# Satellite_Transceiver_Breakout__Swarm_M1.net
KiCad netlist of a schematic drawn in EAGLE
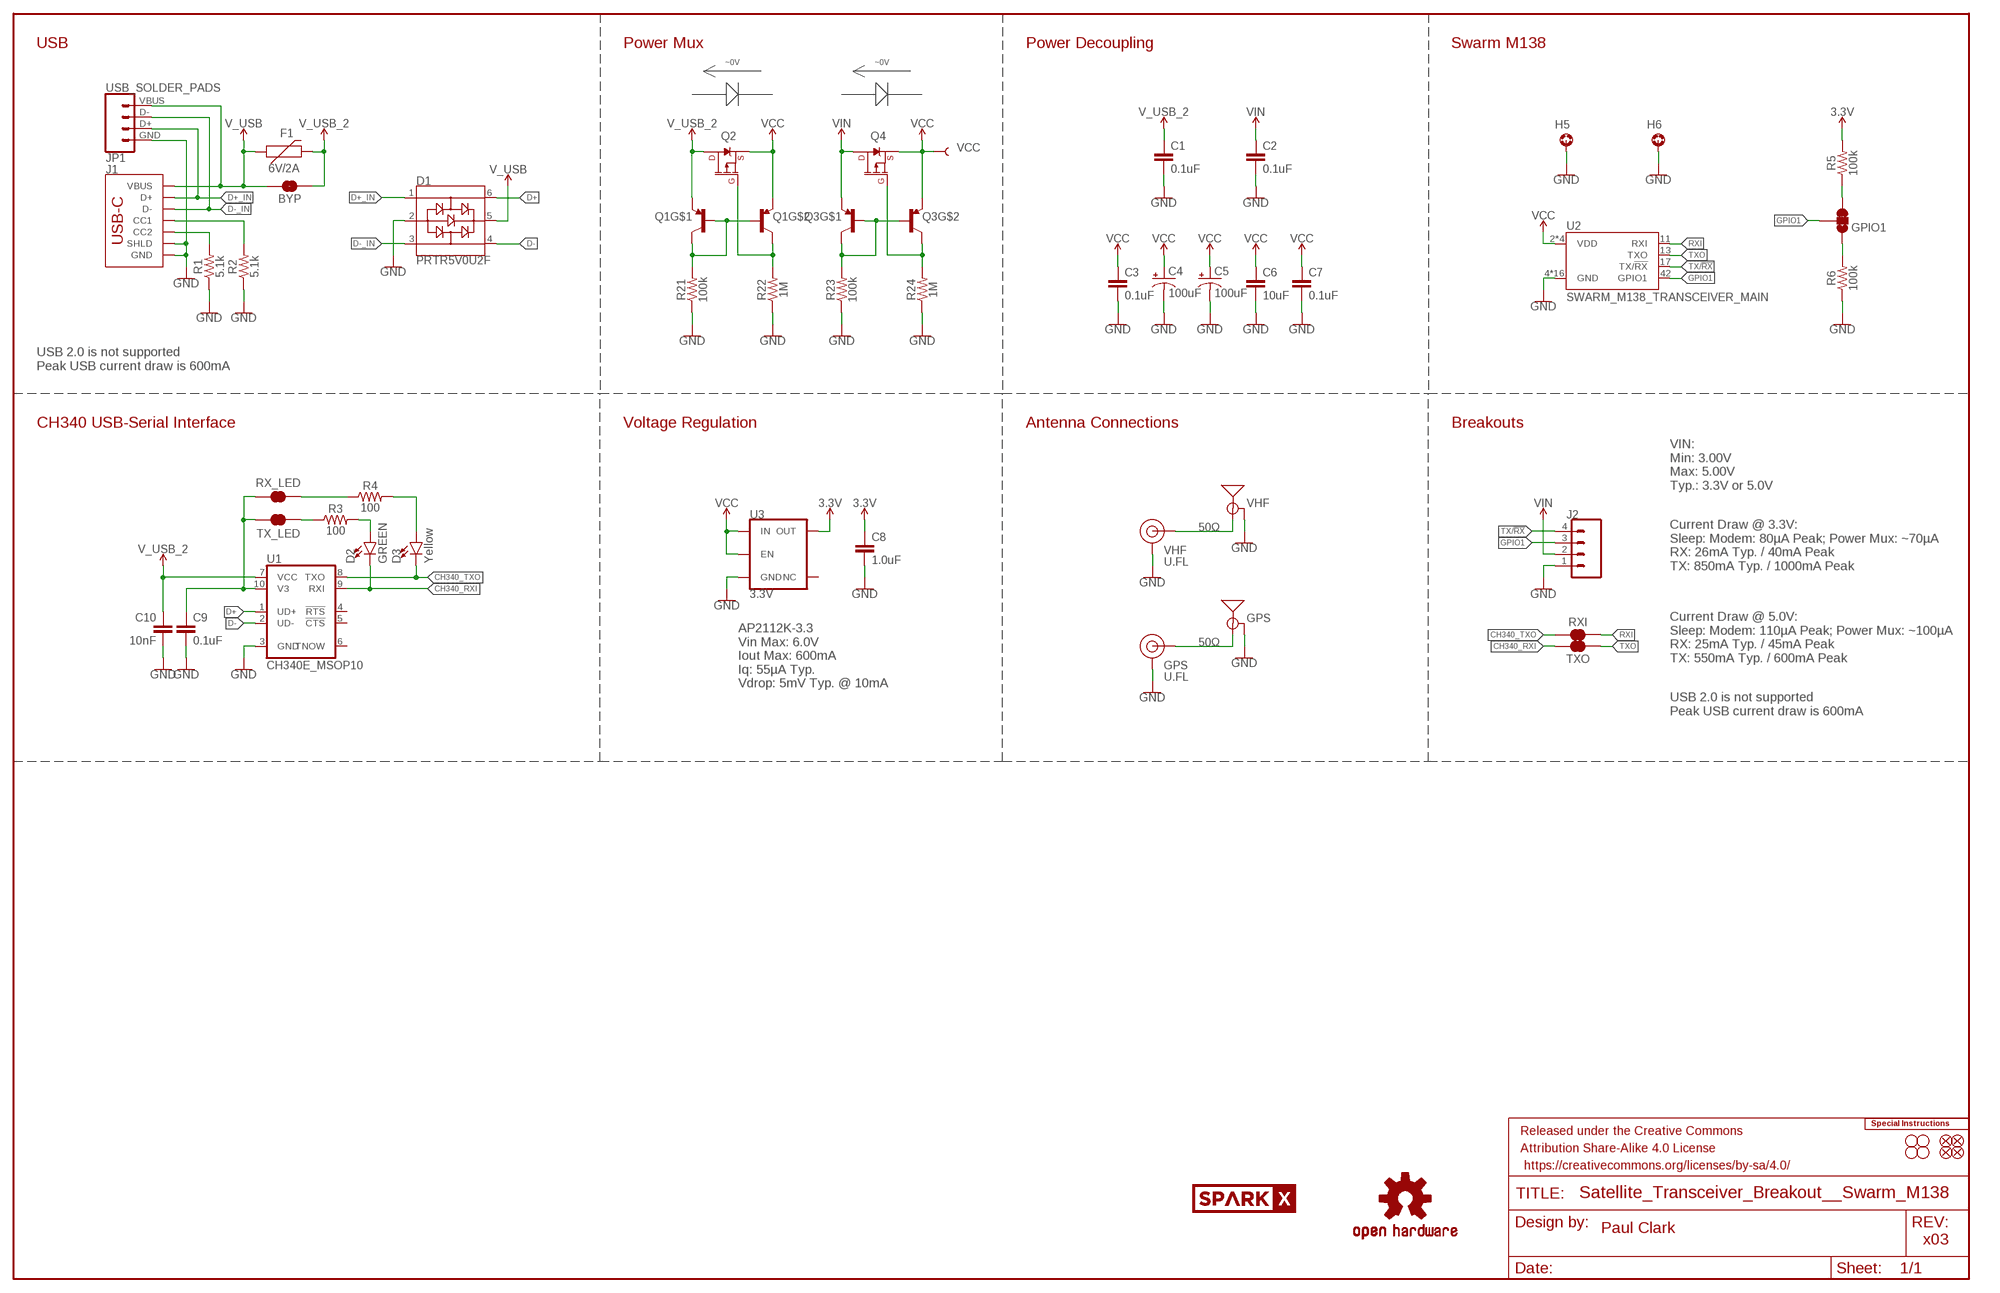
[diagram p0: schematic, sheet 1]

(export (version "E")
  (design (tool "Eeschema 10.0.6"))
  (components
    (comp (ref "BYP")
      (value "JUMPER-SMT_2_NO_SILK")
      (footprint "eagle-import:SMT-JUMPER_2_NO_SILK")
      (libsource (lib "eagle-import") (part "JUMPER-SMT_2_NO_SILK"))
    )
    (comp (ref "C1")
      (value "0.1uF")
      (footprint "eagle-import:0603")
      (libsource (lib "eagle-import") (part "0.1UF-0603-25V-5%"))
    )
    (comp (ref "C2")
      (value "0.1uF")
      (footprint "eagle-import:0603")
      (libsource (lib "eagle-import") (part "0.1UF-0603-25V-5%"))
    )
    (comp (ref "C3")
      (value "0.1uF")
      (footprint "eagle-import:0603")
      (libsource (lib "eagle-import") (part "0.1UF-0603-25V-5%"))
    )
    (comp (ref "C4")
      (value "100uF")
      (footprint "eagle-import:PANASONIC_D")
      (libsource (lib "eagle-import") (part "100UF-POLAR-25V-20%(ELEC)"))
    )
    (comp (ref "C5")
      (value "100uF")
      (footprint "eagle-import:PANASONIC_D")
      (libsource (lib "eagle-import") (part "100UF-POLAR-25V-20%(ELEC)"))
    )
    (comp (ref "C6")
      (value "10uF")
      (footprint "eagle-import:0603")
      (libsource (lib "eagle-import") (part "10UF-0603-6.3V-20%"))
    )
    (comp (ref "C7")
      (value "0.1uF")
      (footprint "eagle-import:0603")
      (libsource (lib "eagle-import") (part "0.1UF-0603-25V-5%"))
    )
    (comp (ref "C8")
      (value "1.0uF")
      (footprint "eagle-import:0603")
      (libsource (lib "eagle-import") (part "1.0UF-0603-16V-10%-X7R"))
    )
    (comp (ref "C9")
      (value "0.1uF")
      (footprint "eagle-import:0603")
      (libsource (lib "eagle-import") (part "0.1UF-0603-25V-5%"))
    )
    (comp (ref "C10")
      (value "10nF")
      (footprint "eagle-import:0603")
      (libsource (lib "eagle-import") (part "10NF-0603-50V-10%"))
    )
    (comp (ref "D1")
      (value "PRTR5V0U2F")
      (footprint "eagle-import:SOT886")
      (libsource (lib "eagle-import") (part "PRTR5V0U2F"))
    )
    (comp (ref "D2")
      (value "GREEN")
      (footprint "eagle-import:LED-0603")
      (libsource (lib "eagle-import") (part "LED-GREEN0603"))
    )
    (comp (ref "D3")
      (value "Yellow")
      (footprint "eagle-import:LED-0603")
      (libsource (lib "eagle-import") (part "LED-YELLOW0603"))
    )
    (comp (ref "E1")
      (value "VHF")
      (footprint "eagle-import:SMA-EDGE")
      (libsource (lib "eagle-import") (part "ANTENNA-SMA-GROUNDEDEDGE_SMA"))
    )
    (comp (ref "E2")
      (value "GPS")
      (footprint "eagle-import:SMA-EDGE")
      (libsource (lib "eagle-import") (part "ANTENNA-SMA-GROUNDEDEDGE_SMA"))
    )
    (comp (ref "F1")
      (value "6V/2A")
      (footprint "eagle-import:1210")
      (libsource (lib "eagle-import") (part "PPTC_6V2A"))
    )
    (comp (ref "FD1")
      (value "FIDUCIAL1X2")
      (footprint "eagle-import:FIDUCIAL-1X2")
      (libsource (lib "eagle-import") (part "FIDUCIAL1X2"))
    )
    (comp (ref "FD2")
      (value "FIDUCIAL1X2")
      (footprint "eagle-import:FIDUCIAL-1X2")
      (libsource (lib "eagle-import") (part "FIDUCIAL1X2"))
    )
    (comp (ref "FD3")
      (value "FIDUCIAL1X2")
      (footprint "eagle-import:FIDUCIAL-1X2")
      (libsource (lib "eagle-import") (part "FIDUCIAL1X2"))
    )
    (comp (ref "FD4")
      (value "FIDUCIAL1X2")
      (footprint "eagle-import:FIDUCIAL-1X2")
      (libsource (lib "eagle-import") (part "FIDUCIAL1X2"))
    )
    (comp (ref "FRAME1")
      (value "FRAME-LEDGER")
      (footprint "eagle-import:CREATIVE_COMMONS")
      (libsource (lib "eagle-import") (part "FRAME-LEDGER"))
    )
    (comp (ref "GPIO1")
      (value "JUMPER-SMT_3_1-NC_TRACE_SILK")
      (footprint "eagle-import:SMT-JUMPER_3_1-NC_TRACE_SILK")
      (libsource (lib "eagle-import") (part "JUMPER-SMT_3_1-NC_TRACE_SILK"))
    )
    (comp (ref "GPS")
      (value "U.FL")
      (footprint "eagle-import:U.FL")
      (libsource (lib "eagle-import") (part "U.FL2PIN"))
    )
    (comp (ref "H1")
      (value "STAND-OFF")
      (footprint "eagle-import:STAND-OFF")
      (libsource (lib "eagle-import") (part "STAND-OFF"))
    )
    (comp (ref "H2")
      (value "STAND-OFF")
      (footprint "eagle-import:STAND-OFF")
      (libsource (lib "eagle-import") (part "STAND-OFF"))
    )
    (comp (ref "H3")
      (value "STAND-OFF")
      (footprint "eagle-import:STAND-OFF")
      (libsource (lib "eagle-import") (part "STAND-OFF"))
    )
    (comp (ref "H4")
      (value "STAND-OFF")
      (footprint "eagle-import:STAND-OFF")
      (libsource (lib "eagle-import") (part "STAND-OFF"))
    )
    (comp (ref "H5")
      (value "STAND-OFF-REFLOW-M2.5_1.5MM_TALL")
      (footprint "eagle-import:STAND-OFF-REFLOW-M2.5")
      (libsource (lib "eagle-import") (part "STAND-OFF-REFLOW-M2.5_1.5MM_TALL"))
    )
    (comp (ref "H6")
      (value "STAND-OFF-REFLOW-M2.5_1.5MM_TALL")
      (footprint "eagle-import:STAND-OFF-REFLOW-M2.5")
      (libsource (lib "eagle-import") (part "STAND-OFF-REFLOW-M2.5_1.5MM_TALL"))
    )
    (comp (ref "J1")
      (value "USB_C_2-LAYER_PADS")
      (footprint "eagle-import:USB-C-16P-2LAYER-PADS")
      (libsource (lib "eagle-import") (part "USB_C_2-LAYER_PADS"))
    )
    (comp (ref "J2")
      (value "CONN_041X04_NO_SILK")
      (footprint "eagle-import:1X04_NO_SILK")
      (libsource (lib "eagle-import") (part "CONN_041X04_NO_SILK"))
    )
    (comp (ref "JP1")
      (value "USB_SOLDER_PADS")
      (footprint "eagle-import:USB-SOLDER-PADS")
      (libsource (lib "eagle-import") (part "USB_SOLDER_PADS"))
    )
    (comp (ref "LOGO1")
      (value "SPECIAL_INSTRUCTIONS-ORDERING")
      (footprint "eagle-import:ORDERING_INSTRUCTIONS")
      (libsource (lib "eagle-import") (part "SPECIAL_INSTRUCTIONS-ORDERING"))
    )
    (comp (ref "LOGO2")
      (value "OSHW-LOGOM")
      (footprint "eagle-import:OSHW-LOGO-M")
      (libsource (lib "eagle-import") (part "OSHW-LOGOM"))
    )
    (comp (ref "LOGO3")
      (value "OSHW-LOGOM")
      (footprint "eagle-import:OSHW-LOGO-M")
      (libsource (lib "eagle-import") (part "OSHW-LOGOM"))
    )
    (comp (ref "Q1")
      (value "TRANS_PNP_DUALSOT-363")
      (footprint "eagle-import:SOT363_PHILIPS")
      (libsource (lib "eagle-import") (part "TRANS_PNP_DUALSOT-363"))
    )
    (comp (ref "Q2")
      (value "20V/4.2A/52mΩ/1.4W")
      (footprint "eagle-import:SOT23-3")
      (libsource (lib "eagle-import") (part "MOSFET_PCH-DMG2305UX-7"))
    )
    (comp (ref "Q3")
      (value "TRANS_PNP_DUALSOT-363")
      (footprint "eagle-import:SOT363_PHILIPS")
      (libsource (lib "eagle-import") (part "TRANS_PNP_DUALSOT-363"))
    )
    (comp (ref "Q4")
      (value "20V/4.2A/52mΩ/1.4W")
      (footprint "eagle-import:SOT23-3")
      (libsource (lib "eagle-import") (part "MOSFET_PCH-DMG2305UX-7"))
    )
    (comp (ref "R1")
      (value "5.1k")
      (footprint "eagle-import:0603")
      (libsource (lib "eagle-import") (part "5.1KOHM5.1KOHM-0603-1/10W-1%"))
    )
    (comp (ref "R2")
      (value "5.1k")
      (footprint "eagle-import:0603")
      (libsource (lib "eagle-import") (part "5.1KOHM5.1KOHM-0603-1/10W-1%"))
    )
    (comp (ref "R3")
      (value "100")
      (footprint "eagle-import:0603")
      (libsource (lib "eagle-import") (part "100OHM-0603-1/10W-1%"))
    )
    (comp (ref "R4")
      (value "100")
      (footprint "eagle-import:0603")
      (libsource (lib "eagle-import") (part "100OHM-0603-1/10W-1%"))
    )
    (comp (ref "R5")
      (value "100k")
      (footprint "eagle-import:0603")
      (libsource (lib "eagle-import") (part "100KOHM-0603-1/10W-1%"))
    )
    (comp (ref "R6")
      (value "100k")
      (footprint "eagle-import:0603")
      (libsource (lib "eagle-import") (part "100KOHM-0603-1/10W-1%"))
    )
    (comp (ref "R21")
      (value "100k")
      (footprint "eagle-import:0603")
      (libsource (lib "eagle-import") (part "100KOHM-0603-1/10W-1%"))
    )
    (comp (ref "R22")
      (value "1M")
      (footprint "eagle-import:0603")
      (libsource (lib "eagle-import") (part "1MOHM-0603-1/4W-5%"))
    )
    (comp (ref "R23")
      (value "100k")
      (footprint "eagle-import:0603")
      (libsource (lib "eagle-import") (part "100KOHM-0603-1/10W-1%"))
    )
    (comp (ref "R24")
      (value "1M")
      (footprint "eagle-import:0603")
      (libsource (lib "eagle-import") (part "1MOHM-0603-1/4W-5%"))
    )
    (comp (ref "RXI")
      (value "JUMPER-COMBO_2_NC_TRACE")
      (footprint "eagle-import:COMBO-JUMPER_2_NC_TRACE")
      (libsource (lib "eagle-import") (part "JUMPER-COMBO_2_NC_TRACE"))
    )
    (comp (ref "RX_LED")
      (value "JUMPER-SMT_2_NC_TRACE_SILK")
      (footprint "eagle-import:SMT-JUMPER_2_NC_TRACE_SILK")
      (libsource (lib "eagle-import") (part "JUMPER-SMT_2_NC_TRACE_SILK"))
    )
    (comp (ref "TXO")
      (value "JUMPER-COMBO_2_NC_TRACE")
      (footprint "eagle-import:COMBO-JUMPER_2_NC_TRACE")
      (libsource (lib "eagle-import") (part "JUMPER-COMBO_2_NC_TRACE"))
    )
    (comp (ref "TX_LED")
      (value "JUMPER-SMT_2_NC_TRACE_SILK")
      (footprint "eagle-import:SMT-JUMPER_2_NC_TRACE_SILK")
      (libsource (lib "eagle-import") (part "JUMPER-SMT_2_NC_TRACE_SILK"))
    )
    (comp (ref "U$1")
      (value "SPARKX-LOGO5")
      (footprint "eagle-import:SPARKX-LARGE")
      (libsource (lib "eagle-import") (part "SPARKX-LOGO5"))
    )
    (comp (ref "U$2")
      (value "SPARKX-LOGO5")
      (footprint "eagle-import:SPARKX-LARGE")
      (libsource (lib "eagle-import") (part "SPARKX-LOGO5"))
    )
    (comp (ref "U1")
      (value "CH340E_MSOP10")
      (footprint "eagle-import:MSOP10")
      (libsource (lib "eagle-import") (part "CH340E_MSOP10"))
    )
    (comp (ref "U2")
      (value "SWARM_M138_TRANSCEIVER_MAIN")
      (footprint "eagle-import:M.2-SWARM-M138-A")
      (libsource (lib "eagle-import") (part "SWARM_M138_TRANSCEIVER_MAIN"))
    )
    (comp (ref "U3")
      (value "3.3V")
      (footprint "eagle-import:SOT23-5")
      (libsource (lib "eagle-import") (part "V_REG_AP2112K-3.3V"))
    )
    (comp (ref "VCC")
      (value "TEST-POINT3X5")
      (footprint "eagle-import:PAD.03X.05")
      (libsource (lib "eagle-import") (part "TEST-POINT3X5"))
    )
    (comp (ref "VHF")
      (value "U.FL")
      (footprint "eagle-import:U.FL")
      (libsource (lib "eagle-import") (part "U.FL2PIN"))
    )
  )
  (nets
    (net (code "1") (name "/TX{slash}~{RX}") (class "Default")
      (node (ref "J2") (pin "4") (pinfunction "4_4") (pintype "passive"))
      (node (ref "U2") (pin "17") (pinfunction "TX/~{RX}_17") (pintype "output"))
    )
    (net (code "2") (name "3.3V") (class "Default")
      (node (ref "C8") (pin "1") (pinfunction "1_1") (pintype "passive"))
      (node (ref "R5") (pin "2") (pinfunction "2_2") (pintype "passive"))
      (node (ref "U3") (pin "5") (pinfunction "OUT_5") (pintype "passive"))
    )
    (net (code "3") (name "CH340_RXI") (class "Default")
      (node (ref "D2") (pin "C") (pinfunction "C_C") (pintype "passive"))
      (node (ref "TXO") (pin "2") (pinfunction "2_2") (pintype "passive"))
      (node (ref "TXO") (pin "4") (pinfunction "2_4") (pintype "passive"))
      (node (ref "U1") (pin "9") (pinfunction "RXI_9") (pintype "bidirectional"))
    )
    (net (code "4") (name "CH340_TXO") (class "Default")
      (node (ref "D3") (pin "C") (pinfunction "C_C") (pintype "passive"))
      (node (ref "RXI") (pin "1") (pinfunction "1_1") (pintype "passive"))
      (node (ref "RXI") (pin "3") (pinfunction "1_3") (pintype "passive"))
      (node (ref "U1") (pin "8") (pinfunction "TXO_8") (pintype "bidirectional"))
    )
    (net (code "5") (name "D+") (class "Default")
      (node (ref "D1") (pin "6") (pinfunction "6_6") (pintype "bidirectional"))
      (node (ref "U1") (pin "1") (pinfunction "UD+_1") (pintype "bidirectional"))
    )
    (net (code "6") (name "D+_IN") (class "Default")
      (node (ref "D1") (pin "1") (pinfunction "1_1") (pintype "bidirectional"))
      (node (ref "J1") (pin "A6") (pinfunction "D+_A6") (pintype "bidirectional"))
      (node (ref "J1") (pin "B6") (pinfunction "D+_B6") (pintype "bidirectional"))
      (node (ref "JP1") (pin "D+") (pinfunction "3_D+") (pintype "passive"))
    )
    (net (code "7") (name "D-") (class "Default")
      (node (ref "D1") (pin "4") (pinfunction "4_4") (pintype "bidirectional"))
      (node (ref "U1") (pin "2") (pinfunction "UD-_2") (pintype "bidirectional"))
    )
    (net (code "8") (name "D-_IN") (class "Default")
      (node (ref "D1") (pin "3") (pinfunction "3_3") (pintype "bidirectional"))
      (node (ref "J1") (pin "A7") (pinfunction "D-_A7") (pintype "bidirectional"))
      (node (ref "J1") (pin "B7") (pinfunction "D-_B7") (pintype "bidirectional"))
      (node (ref "JP1") (pin "D-") (pinfunction "2_D-") (pintype "passive"))
    )
    (net (code "9") (name "GND") (class "Default")
      (node (ref "C1") (pin "2") (pinfunction "2_2") (pintype "passive"))
      (node (ref "C10") (pin "2") (pinfunction "2_2") (pintype "passive"))
      (node (ref "C2") (pin "2") (pinfunction "2_2") (pintype "passive"))
      (node (ref "C3") (pin "2") (pinfunction "2_2") (pintype "passive"))
      (node (ref "C4") (pin "-") (pinfunction "-_-") (pintype "passive"))
      (node (ref "C5") (pin "-") (pinfunction "-_-") (pintype "passive"))
      (node (ref "C6") (pin "2") (pinfunction "2_2") (pintype "passive"))
      (node (ref "C7") (pin "2") (pinfunction "2_2") (pintype "passive"))
      (node (ref "C8") (pin "2") (pinfunction "2_2") (pintype "passive"))
      (node (ref "C9") (pin "2") (pinfunction "2_2") (pintype "passive"))
      (node (ref "D1") (pin "2") (pinfunction "2_2") (pintype "power_in"))
      (node (ref "E1") (pin "GND@0") (pinfunction "GND_GND@0") (pintype "bidirectional"))
      (node (ref "E1") (pin "GND@1") (pinfunction "GND_GND@1") (pintype "bidirectional"))
      (node (ref "E1") (pin "GND@2") (pinfunction "GND_GND@2") (pintype "bidirectional"))
      (node (ref "E1") (pin "GND@3") (pinfunction "GND_GND@3") (pintype "bidirectional"))
      (node (ref "E2") (pin "GND@0") (pinfunction "GND_GND@0") (pintype "bidirectional"))
      (node (ref "E2") (pin "GND@1") (pinfunction "GND_GND@1") (pintype "bidirectional"))
      (node (ref "E2") (pin "GND@2") (pinfunction "GND_GND@2") (pintype "bidirectional"))
      (node (ref "E2") (pin "GND@3") (pinfunction "GND_GND@3") (pintype "bidirectional"))
      (node (ref "GPS") (pin "1") (pinfunction "GND_1") (pintype "bidirectional"))
      (node (ref "GPS") (pin "2") (pinfunction "GND_2") (pintype "bidirectional"))
      (node (ref "H5") (pin "1") (pinfunction "1_1") (pintype "bidirectional"))
      (node (ref "H6") (pin "1") (pinfunction "1_1") (pintype "bidirectional"))
      (node (ref "J1") (pin "GND") (pinfunction "GND_GND") (pintype "bidirectional"))
      (node (ref "J1") (pin "GND2") (pinfunction "GND_GND2") (pintype "bidirectional"))
      (node (ref "J1") (pin "SHLD1") (pinfunction "SHLD_SHLD1") (pintype "bidirectional"))
      (node (ref "J1") (pin "SHLD2") (pinfunction "SHLD_SHLD2") (pintype "bidirectional"))
      (node (ref "J1") (pin "SHLD3") (pinfunction "SHLD_SHLD3") (pintype "bidirectional"))
      (node (ref "J1") (pin "SHLD4") (pinfunction "SHLD_SHLD4") (pintype "bidirectional"))
      (node (ref "J2") (pin "1") (pinfunction "1_1") (pintype "passive"))
      (node (ref "JP1") (pin "GND") (pinfunction "4_GND") (pintype "passive"))
      (node (ref "R1") (pin "1") (pinfunction "1_1") (pintype "passive"))
      (node (ref "R2") (pin "1") (pinfunction "1_1") (pintype "passive"))
      (node (ref "R21") (pin "1") (pinfunction "1_1") (pintype "passive"))
      (node (ref "R22") (pin "1") (pinfunction "1_1") (pintype "passive"))
      (node (ref "R23") (pin "1") (pinfunction "1_1") (pintype "passive"))
      (node (ref "R24") (pin "1") (pinfunction "1_1") (pintype "passive"))
      (node (ref "R6") (pin "1") (pinfunction "1_1") (pintype "passive"))
      (node (ref "U1") (pin "3") (pinfunction "GND_3") (pintype "bidirectional"))
      (node (ref "U2") (pin "15") (pinfunction "GND_15") (pintype "power_in"))
      (node (ref "U2") (pin "18") (pinfunction "GND_18") (pintype "power_in"))
      (node (ref "U2") (pin "21") (pinfunction "GND_21") (pintype "power_in"))
      (node (ref "U2") (pin "26") (pinfunction "GND_26") (pintype "power_in"))
      (node (ref "U2") (pin "27") (pinfunction "GND_27") (pintype "power_in"))
      (node (ref "U2") (pin "29") (pinfunction "GND_29") (pintype "power_in"))
      (node (ref "U2") (pin "34") (pinfunction "GND_34") (pintype "power_in"))
      (node (ref "U2") (pin "35") (pinfunction "GND_35") (pintype "power_in"))
      (node (ref "U2") (pin "37") (pinfunction "GND_37") (pintype "power_in"))
      (node (ref "U2") (pin "4") (pinfunction "GND_4") (pintype "power_in"))
      (node (ref "U2") (pin "40") (pinfunction "GND_40") (pintype "power_in"))
      (node (ref "U2") (pin "43") (pinfunction "GND_43") (pintype "power_in"))
      (node (ref "U2") (pin "50") (pinfunction "GND_50") (pintype "power_in"))
      (node (ref "U2") (pin "9") (pinfunction "GND_9") (pintype "power_in"))
      (node (ref "U2") (pin "A1") (pinfunction "GND_A1") (pintype "power_in"))
      (node (ref "U2") (pin "A2") (pinfunction "GND_A2") (pintype "power_in"))
      (node (ref "U3") (pin "2") (pinfunction "GND_2") (pintype "input"))
      (node (ref "VHF") (pin "1") (pinfunction "GND_1") (pintype "bidirectional"))
      (node (ref "VHF") (pin "2") (pinfunction "GND_2") (pintype "bidirectional"))
    )
    (net (code "10") (name "GPIO1") (class "Default")
      (node (ref "GPIO1") (pin "2") (pinfunction "2_2") (pintype "passive"))
      (node (ref "J2") (pin "3") (pinfunction "3_3") (pintype "passive"))
      (node (ref "U2") (pin "42") (pinfunction "GPIO1_42") (pintype "bidirectional"))
    )
    (net (code "11") (name "Net-(D2-PadA)") (class "Default")
      (node (ref "D2") (pin "A") (pinfunction "A_A") (pintype "passive"))
      (node (ref "R3") (pin "2") (pinfunction "2_2") (pintype "passive"))
    )
    (net (code "12") (name "Net-(D3-PadA)") (class "Default")
      (node (ref "D3") (pin "A") (pinfunction "A_A") (pintype "passive"))
      (node (ref "R4") (pin "2") (pinfunction "2_2") (pintype "passive"))
    )
    (net (code "13") (name "Net-(E1-SIGNAL)") (class "Default")
      (node (ref "E1") (pin "SIG") (pinfunction "SIGNAL_SIG") (pintype "bidirectional"))
      (node (ref "VHF") (pin "FEED") (pinfunction "SIGNAL_FEED") (pintype "bidirectional"))
    )
    (net (code "14") (name "Net-(E2-SIGNAL)") (class "Default")
      (node (ref "E2") (pin "SIG") (pinfunction "SIGNAL_SIG") (pintype "bidirectional"))
      (node (ref "GPS") (pin "FEED") (pinfunction "SIGNAL_FEED") (pintype "bidirectional"))
    )
    (net (code "15") (name "Net-(GPIO1-Pad1)") (class "Default")
      (node (ref "GPIO1") (pin "1") (pinfunction "1_1") (pintype "passive"))
      (node (ref "R6") (pin "2") (pinfunction "2_2") (pintype "passive"))
    )
    (net (code "16") (name "Net-(GPIO1-Pad3)") (class "Default")
      (node (ref "GPIO1") (pin "3") (pinfunction "3_3") (pintype "passive"))
      (node (ref "R5") (pin "1") (pinfunction "1_1") (pintype "passive"))
    )
    (net (code "17") (name "Net-(J1-CC1)") (class "Default")
      (node (ref "J1") (pin "A5") (pinfunction "CC1_A5") (pintype "bidirectional"))
      (node (ref "R2") (pin "2") (pinfunction "2_2") (pintype "passive"))
    )
    (net (code "18") (name "Net-(J1-CC2)") (class "Default")
      (node (ref "J1") (pin "B5") (pinfunction "CC2_B5") (pintype "bidirectional"))
      (node (ref "R1") (pin "2") (pinfunction "2_2") (pintype "passive"))
    )
    (net (code "19") (name "Net-(Q1A-B)") (class "Default")
      (node (ref "Q1") (pin "2") (pinfunction "B_2") (pintype "passive"))
      (node (ref "Q1") (pin "5") (pinfunction "B_5") (pintype "passive"))
      (node (ref "Q1") (pin "6") (pinfunction "C_6") (pintype "passive"))
      (node (ref "R21") (pin "2") (pinfunction "2_2") (pintype "passive"))
    )
    (net (code "20") (name "Net-(Q1B-C)") (class "Default")
      (node (ref "Q1") (pin "3") (pinfunction "C_3") (pintype "passive"))
      (node (ref "Q2") (pin "1") (pinfunction "G_1") (pintype "bidirectional"))
      (node (ref "R22") (pin "2") (pinfunction "2_2") (pintype "passive"))
    )
    (net (code "21") (name "Net-(Q3A-B)") (class "Default")
      (node (ref "Q3") (pin "2") (pinfunction "B_2") (pintype "passive"))
      (node (ref "Q3") (pin "5") (pinfunction "B_5") (pintype "passive"))
      (node (ref "Q3") (pin "6") (pinfunction "C_6") (pintype "passive"))
      (node (ref "R23") (pin "2") (pinfunction "2_2") (pintype "passive"))
    )
    (net (code "22") (name "Net-(Q3B-C)") (class "Default")
      (node (ref "Q3") (pin "3") (pinfunction "C_3") (pintype "passive"))
      (node (ref "Q4") (pin "1") (pinfunction "G_1") (pintype "bidirectional"))
      (node (ref "R24") (pin "2") (pinfunction "2_2") (pintype "passive"))
    )
    (net (code "23") (name "Net-(R3-Pad1)") (class "Default")
      (node (ref "R3") (pin "1") (pinfunction "1_1") (pintype "passive"))
      (node (ref "TX_LED") (pin "1") (pinfunction "1_1") (pintype "passive"))
    )
    (net (code "24") (name "Net-(R4-Pad1)") (class "Default")
      (node (ref "R4") (pin "1") (pinfunction "1_1") (pintype "passive"))
      (node (ref "RX_LED") (pin "2") (pinfunction "2_2") (pintype "passive"))
    )
    (net (code "25") (name "Net-(U1-V3)") (class "Default")
      (node (ref "C9") (pin "1") (pinfunction "1_1") (pintype "passive"))
      (node (ref "RX_LED") (pin "1") (pinfunction "1_1") (pintype "passive"))
      (node (ref "TX_LED") (pin "2") (pinfunction "2_2") (pintype "passive"))
      (node (ref "U1") (pin "10") (pinfunction "V3_10") (pintype "bidirectional"))
    )
    (net (code "26") (name "RXI") (class "Default")
      (node (ref "RXI") (pin "2") (pinfunction "2_2") (pintype "passive"))
      (node (ref "RXI") (pin "4") (pinfunction "2_4") (pintype "passive"))
      (node (ref "U2") (pin "11") (pinfunction "RXI_11") (pintype "input"))
    )
    (net (code "27") (name "TXO") (class "Default")
      (node (ref "TXO") (pin "1") (pinfunction "1_1") (pintype "passive"))
      (node (ref "TXO") (pin "3") (pinfunction "1_3") (pintype "passive"))
      (node (ref "U2") (pin "13") (pinfunction "TXO_13") (pintype "output"))
    )
    (net (code "28") (name "VCC") (class "Default")
      (node (ref "C3") (pin "1") (pinfunction "1_1") (pintype "passive"))
      (node (ref "C4") (pin "+") (pinfunction "+_+") (pintype "passive"))
      (node (ref "C5") (pin "+") (pinfunction "+_+") (pintype "passive"))
      (node (ref "C6") (pin "1") (pinfunction "1_1") (pintype "passive"))
      (node (ref "C7") (pin "1") (pinfunction "1_1") (pintype "passive"))
      (node (ref "Q1") (pin "4") (pinfunction "E_4") (pintype "passive"))
      (node (ref "Q2") (pin "2") (pinfunction "S_2") (pintype "bidirectional"))
      (node (ref "Q3") (pin "4") (pinfunction "E_4") (pintype "passive"))
      (node (ref "Q4") (pin "2") (pinfunction "S_2") (pintype "bidirectional"))
      (node (ref "U2") (pin "2") (pinfunction "VDD_2") (pintype "power_in"))
      (node (ref "U2") (pin "39") (pinfunction "VDD_39") (pintype "power_in"))
      (node (ref "U2") (pin "41") (pinfunction "VDD_41") (pintype "power_in"))
      (node (ref "U2") (pin "52") (pinfunction "VDD_52") (pintype "power_in"))
      (node (ref "U3") (pin "1") (pinfunction "IN_1") (pintype "input"))
      (node (ref "U3") (pin "3") (pinfunction "EN_3") (pintype "input"))
      (node (ref "VCC") (pin "1") (pinfunction "1_1") (pintype "bidirectional"))
    )
    (net (code "29") (name "VIN") (class "Default")
      (node (ref "C2") (pin "1") (pinfunction "1_1") (pintype "passive"))
      (node (ref "J2") (pin "2") (pinfunction "2_2") (pintype "passive"))
      (node (ref "Q3") (pin "1") (pinfunction "E_1") (pintype "passive"))
      (node (ref "Q4") (pin "3") (pinfunction "D_3") (pintype "bidirectional"))
    )
    (net (code "30") (name "V_USB") (class "Default")
      (node (ref "BYP") (pin "2") (pinfunction "2_2") (pintype "passive"))
      (node (ref "D1") (pin "5") (pinfunction "5_5") (pintype "power_in"))
      (node (ref "F1") (pin "1") (pinfunction "1_1") (pintype "bidirectional"))
      (node (ref "J1") (pin "VBUS1") (pinfunction "VBUS_VBUS1") (pintype "bidirectional"))
      (node (ref "J1") (pin "VBUS2") (pinfunction "VBUS_VBUS2") (pintype "bidirectional"))
      (node (ref "JP1") (pin "VBUS") (pinfunction "1_VBUS") (pintype "passive"))
    )
    (net (code "31") (name "V_USB_2") (class "Default")
      (node (ref "BYP") (pin "1") (pinfunction "1_1") (pintype "passive"))
      (node (ref "C1") (pin "1") (pinfunction "1_1") (pintype "passive"))
      (node (ref "C10") (pin "1") (pinfunction "1_1") (pintype "passive"))
      (node (ref "F1") (pin "2") (pinfunction "2_2") (pintype "bidirectional"))
      (node (ref "Q1") (pin "1") (pinfunction "E_1") (pintype "passive"))
      (node (ref "Q2") (pin "3") (pinfunction "D_3") (pintype "bidirectional"))
      (node (ref "U1") (pin "7") (pinfunction "VCC_7") (pintype "bidirectional"))
    )
    (net (code "32") (name "unconnected-(U1-TNOW-Pad6)") (class "Default")
      (node (ref "U1") (pin "6") (pinfunction "TNOW_6") (pintype "bidirectional"))
    )
    (net (code "33") (name "unconnected-(U1-~{CTS}-Pad5)") (class "Default")
      (node (ref "U1") (pin "5") (pinfunction "~{CTS}_5") (pintype "bidirectional"))
    )
    (net (code "34") (name "unconnected-(U1-~{RTS}-Pad4)") (class "Default")
      (node (ref "U1") (pin "4") (pinfunction "~{RTS}_4") (pintype "bidirectional"))
    )
    (net (code "35") (name "unconnected-(U3-NC-Pad4)") (class "Default")
      (node (ref "U3") (pin "4") (pinfunction "NC_4") (pintype "no_connect"))
    )
  )
)
